# SNES_JAMMA.net
KiCad netlist of a schematic drawn in EAGLE
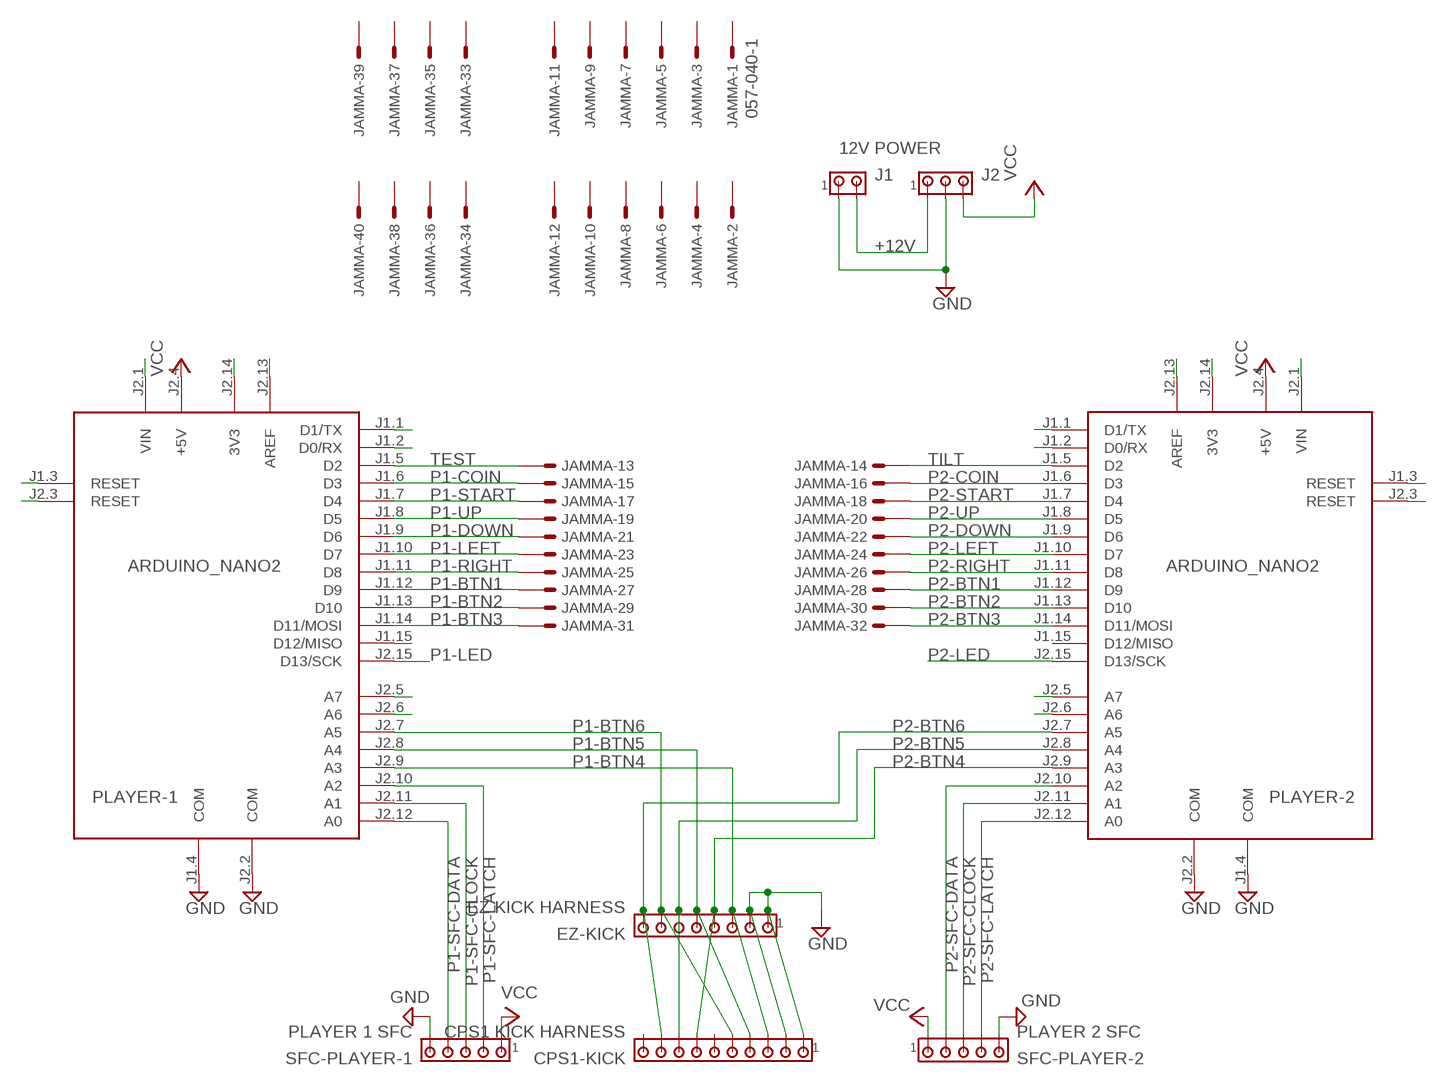
[diagram p0: schematic, sheet 1]

(export (version "E")
  (design (tool "Eeschema 10.0.6"))
  (components
    (comp (ref "CPS1-KICK")
      (value "CPS1 KICK HARNESS")
      (footprint "eagle-import:10X10MTA")
      (libsource (lib "eagle-import") (part "MTA10-100"))
    )
    (comp (ref "EZ-KICK")
      (value "EZ KICK HARNESS")
      (footprint "eagle-import:10X08MTA")
      (libsource (lib "eagle-import") (part "MTA08-100"))
    )
    (comp (ref "J1")
      (value "12V POWER")
      (footprint "eagle-import:10X02MTA")
      (libsource (lib "eagle-import") (part "MTA02-100"))
    )
    (comp (ref "J2")
      (value "MTA03-100")
      (footprint "eagle-import:10X03MTA")
      (libsource (lib "eagle-import") (part "MTA03-100"))
    )
    (comp (ref "JAMMA")
      (value "057-040-1")
      (footprint "eagle-import:057-040-1")
      (libsource (lib "eagle-import") (part "057-040-1"))
    )
    (comp (ref "PLAYER-1")
      (value "ARDUINO_NANO2")
      (footprint "eagle-import:ARDUINO_NANO2")
      (libsource (lib "eagle-import") (part "ARDUINO_NANO2"))
    )
    (comp (ref "PLAYER-2")
      (value "ARDUINO_NANO2")
      (footprint "eagle-import:ARDUINO_NANO2")
      (libsource (lib "eagle-import") (part "ARDUINO_NANO2"))
    )
    (comp (ref "SFC-PLAYER-1")
      (value "PLAYER 1 SFC")
      (footprint "eagle-import:10X05MTA")
      (libsource (lib "eagle-import") (part "MTA05-100"))
    )
    (comp (ref "SFC-PLAYER-2")
      (value "PLAYER 2 SFC")
      (footprint "eagle-import:10X05MTA")
      (libsource (lib "eagle-import") (part "MTA05-100"))
    )
  )
  (nets
    (net (code "1") (name "/+12V") (class "Default")
      (node (ref "J1") (pin "2") (pinfunction "2_2") (pintype "passive"))
      (node (ref "J2") (pin "1") (pinfunction "1_1") (pintype "passive"))
    )
    (net (code "2") (name "/P1-BTN1") (class "Default")
      (node (ref "JAMMA") (pin "27") (pinfunction "S_27") (pintype "passive"))
      (node (ref "PLAYER-1") (pin "J1.12") (pinfunction "D9_J1.12") (pintype "bidirectional"))
    )
    (net (code "3") (name "/P1-BTN2") (class "Default")
      (node (ref "JAMMA") (pin "29") (pinfunction "S_29") (pintype "passive"))
      (node (ref "PLAYER-1") (pin "J1.13") (pinfunction "D10_J1.13") (pintype "bidirectional"))
    )
    (net (code "4") (name "/P1-BTN3") (class "Default")
      (node (ref "JAMMA") (pin "31") (pinfunction "S_31") (pintype "passive"))
      (node (ref "PLAYER-1") (pin "J1.14") (pinfunction "D11/MOSI_J1.14") (pintype "bidirectional"))
    )
    (net (code "5") (name "/P1-BTN4") (class "Default")
      (node (ref "CPS1-KICK") (pin "3") (pinfunction "3_3") (pintype "passive"))
      (node (ref "EZ-KICK") (pin "3") (pinfunction "3_3") (pintype "passive"))
      (node (ref "PLAYER-1") (pin "J2.9") (pinfunction "A3_J2.9") (pintype "bidirectional"))
    )
    (net (code "6") (name "/P1-BTN5") (class "Default")
      (node (ref "CPS1-KICK") (pin "4") (pinfunction "4_4") (pintype "passive"))
      (node (ref "EZ-KICK") (pin "5") (pinfunction "5_5") (pintype "passive"))
      (node (ref "PLAYER-1") (pin "J2.8") (pinfunction "A4_J2.8") (pintype "bidirectional"))
    )
    (net (code "7") (name "/P1-BTN6") (class "Default")
      (node (ref "CPS1-KICK") (pin "5") (pinfunction "5_5") (pintype "passive"))
      (node (ref "EZ-KICK") (pin "7") (pinfunction "7_7") (pintype "passive"))
      (node (ref "PLAYER-1") (pin "J2.7") (pinfunction "A5_J2.7") (pintype "bidirectional"))
    )
    (net (code "8") (name "/P1-COIN") (class "Default")
      (node (ref "JAMMA") (pin "15") (pinfunction "S_15") (pintype "passive"))
      (node (ref "PLAYER-1") (pin "J1.6") (pinfunction "D3_J1.6") (pintype "bidirectional"))
    )
    (net (code "9") (name "/P1-DOWN") (class "Default")
      (node (ref "JAMMA") (pin "21") (pinfunction "S_21") (pintype "passive"))
      (node (ref "PLAYER-1") (pin "J1.9") (pinfunction "D6_J1.9") (pintype "bidirectional"))
    )
    (net (code "10") (name "/P1-LED") (class "Default")
      (node (ref "PLAYER-1") (pin "J2.15") (pinfunction "D13/SCK_J2.15") (pintype "bidirectional"))
    )
    (net (code "11") (name "/P1-LEFT") (class "Default")
      (node (ref "JAMMA") (pin "23") (pinfunction "S_23") (pintype "passive"))
      (node (ref "PLAYER-1") (pin "J1.10") (pinfunction "D7_J1.10") (pintype "bidirectional"))
    )
    (net (code "12") (name "/P1-RIGHT") (class "Default")
      (node (ref "JAMMA") (pin "25") (pinfunction "S_25") (pintype "passive"))
      (node (ref "PLAYER-1") (pin "J1.11") (pinfunction "D8_J1.11") (pintype "bidirectional"))
    )
    (net (code "13") (name "/P1-SFC-CLOCK") (class "Default")
      (node (ref "PLAYER-1") (pin "J2.11") (pinfunction "A1_J2.11") (pintype "bidirectional"))
      (node (ref "SFC-PLAYER-1") (pin "3") (pinfunction "3_3") (pintype "passive"))
    )
    (net (code "14") (name "/P1-SFC-DATA") (class "Default")
      (node (ref "PLAYER-1") (pin "J2.12") (pinfunction "A0_J2.12") (pintype "bidirectional"))
      (node (ref "SFC-PLAYER-1") (pin "4") (pinfunction "4_4") (pintype "passive"))
    )
    (net (code "15") (name "/P1-SFC-LATCH") (class "Default")
      (node (ref "PLAYER-1") (pin "J2.10") (pinfunction "A2_J2.10") (pintype "bidirectional"))
      (node (ref "SFC-PLAYER-1") (pin "2") (pinfunction "2_2") (pintype "passive"))
    )
    (net (code "16") (name "/P1-START") (class "Default")
      (node (ref "JAMMA") (pin "17") (pinfunction "S_17") (pintype "passive"))
      (node (ref "PLAYER-1") (pin "J1.7") (pinfunction "D4_J1.7") (pintype "bidirectional"))
    )
    (net (code "17") (name "/P1-UP") (class "Default")
      (node (ref "JAMMA") (pin "19") (pinfunction "S_19") (pintype "passive"))
      (node (ref "PLAYER-1") (pin "J1.8") (pinfunction "D5_J1.8") (pintype "bidirectional"))
    )
    (net (code "18") (name "/P2-BTN1") (class "Default")
      (node (ref "JAMMA") (pin "28") (pinfunction "S_28") (pintype "passive"))
      (node (ref "PLAYER-2") (pin "J1.12") (pinfunction "D9_J1.12") (pintype "bidirectional"))
    )
    (net (code "19") (name "/P2-BTN2") (class "Default")
      (node (ref "JAMMA") (pin "30") (pinfunction "S_30") (pintype "passive"))
      (node (ref "PLAYER-2") (pin "J1.13") (pinfunction "D10_J1.13") (pintype "bidirectional"))
    )
    (net (code "20") (name "/P2-BTN3") (class "Default")
      (node (ref "JAMMA") (pin "32") (pinfunction "S_32") (pintype "passive"))
      (node (ref "PLAYER-2") (pin "J1.14") (pinfunction "D11/MOSI_J1.14") (pintype "bidirectional"))
    )
    (net (code "21") (name "/P2-BTN4") (class "Default")
      (node (ref "CPS1-KICK") (pin "7") (pinfunction "7_7") (pintype "passive"))
      (node (ref "EZ-KICK") (pin "4") (pinfunction "4_4") (pintype "passive"))
      (node (ref "PLAYER-2") (pin "J2.9") (pinfunction "A3_J2.9") (pintype "bidirectional"))
    )
    (net (code "22") (name "/P2-BTN5") (class "Default")
      (node (ref "CPS1-KICK") (pin "8") (pinfunction "8_8") (pintype "passive"))
      (node (ref "EZ-KICK") (pin "6") (pinfunction "6_6") (pintype "passive"))
      (node (ref "PLAYER-2") (pin "J2.8") (pinfunction "A4_J2.8") (pintype "bidirectional"))
    )
    (net (code "23") (name "/P2-BTN6") (class "Default")
      (node (ref "CPS1-KICK") (pin "9") (pinfunction "9_9") (pintype "passive"))
      (node (ref "EZ-KICK") (pin "8") (pinfunction "8_8") (pintype "passive"))
      (node (ref "PLAYER-2") (pin "J2.7") (pinfunction "A5_J2.7") (pintype "bidirectional"))
    )
    (net (code "24") (name "/P2-COIN") (class "Default")
      (node (ref "JAMMA") (pin "16") (pinfunction "S_16") (pintype "passive"))
      (node (ref "PLAYER-2") (pin "J1.6") (pinfunction "D3_J1.6") (pintype "bidirectional"))
    )
    (net (code "25") (name "/P2-DOWN") (class "Default")
      (node (ref "JAMMA") (pin "22") (pinfunction "S_22") (pintype "passive"))
      (node (ref "PLAYER-2") (pin "J1.9") (pinfunction "D6_J1.9") (pintype "bidirectional"))
    )
    (net (code "26") (name "/P2-LED") (class "Default")
      (node (ref "PLAYER-2") (pin "J2.15") (pinfunction "D13/SCK_J2.15") (pintype "bidirectional"))
    )
    (net (code "27") (name "/P2-LEFT") (class "Default")
      (node (ref "JAMMA") (pin "24") (pinfunction "S_24") (pintype "passive"))
      (node (ref "PLAYER-2") (pin "J1.10") (pinfunction "D7_J1.10") (pintype "bidirectional"))
    )
    (net (code "28") (name "/P2-RIGHT") (class "Default")
      (node (ref "JAMMA") (pin "26") (pinfunction "S_26") (pintype "passive"))
      (node (ref "PLAYER-2") (pin "J1.11") (pinfunction "D8_J1.11") (pintype "bidirectional"))
    )
    (net (code "29") (name "/P2-SFC-CLOCK") (class "Default")
      (node (ref "PLAYER-2") (pin "J2.11") (pinfunction "A1_J2.11") (pintype "bidirectional"))
      (node (ref "SFC-PLAYER-2") (pin "3") (pinfunction "3_3") (pintype "passive"))
    )
    (net (code "30") (name "/P2-SFC-DATA") (class "Default")
      (node (ref "PLAYER-2") (pin "J2.12") (pinfunction "A0_J2.12") (pintype "bidirectional"))
      (node (ref "SFC-PLAYER-2") (pin "4") (pinfunction "4_4") (pintype "passive"))
    )
    (net (code "31") (name "/P2-SFC-LATCH") (class "Default")
      (node (ref "PLAYER-2") (pin "J2.10") (pinfunction "A2_J2.10") (pintype "bidirectional"))
      (node (ref "SFC-PLAYER-2") (pin "2") (pinfunction "2_2") (pintype "passive"))
    )
    (net (code "32") (name "/P2-START") (class "Default")
      (node (ref "JAMMA") (pin "18") (pinfunction "S_18") (pintype "passive"))
      (node (ref "PLAYER-2") (pin "J1.7") (pinfunction "D4_J1.7") (pintype "bidirectional"))
    )
    (net (code "33") (name "/P2-UP") (class "Default")
      (node (ref "JAMMA") (pin "20") (pinfunction "S_20") (pintype "passive"))
      (node (ref "PLAYER-2") (pin "J1.8") (pinfunction "D5_J1.8") (pintype "bidirectional"))
    )
    (net (code "34") (name "/TEST") (class "Default")
      (node (ref "JAMMA") (pin "13") (pinfunction "S_13") (pintype "passive"))
      (node (ref "PLAYER-1") (pin "J1.5") (pinfunction "D2_J1.5") (pintype "bidirectional"))
    )
    (net (code "35") (name "/TILT") (class "Default")
      (node (ref "JAMMA") (pin "14") (pinfunction "S_14") (pintype "passive"))
      (node (ref "PLAYER-2") (pin "J1.5") (pinfunction "D2_J1.5") (pintype "bidirectional"))
    )
    (net (code "36") (name "GND") (class "Default")
      (node (ref "CPS1-KICK") (pin "1") (pinfunction "1_1") (pintype "passive"))
      (node (ref "CPS1-KICK") (pin "2") (pinfunction "2_2") (pintype "passive"))
      (node (ref "EZ-KICK") (pin "1") (pinfunction "1_1") (pintype "passive"))
      (node (ref "EZ-KICK") (pin "2") (pinfunction "2_2") (pintype "passive"))
      (node (ref "J1") (pin "1") (pinfunction "1_1") (pintype "passive"))
      (node (ref "J2") (pin "2") (pinfunction "2_2") (pintype "passive"))
      (node (ref "PLAYER-1") (pin "J1.4") (pinfunction "COM_J1.4") (pintype "power_in"))
      (node (ref "PLAYER-1") (pin "J2.2") (pinfunction "COM_J2.2") (pintype "power_in"))
      (node (ref "PLAYER-2") (pin "J1.4") (pinfunction "COM_J1.4") (pintype "power_in"))
      (node (ref "PLAYER-2") (pin "J2.2") (pinfunction "COM_J2.2") (pintype "power_in"))
      (node (ref "SFC-PLAYER-1") (pin "5") (pinfunction "5_5") (pintype "passive"))
      (node (ref "SFC-PLAYER-2") (pin "5") (pinfunction "5_5") (pintype "passive"))
    )
    (net (code "37") (name "VCC") (class "Default")
      (node (ref "J2") (pin "3") (pinfunction "3_3") (pintype "passive"))
      (node (ref "PLAYER-1") (pin "J2.4") (pinfunction "+5V_J2.4") (pintype "power_in"))
      (node (ref "PLAYER-2") (pin "J2.4") (pinfunction "+5V_J2.4") (pintype "power_in"))
      (node (ref "SFC-PLAYER-1") (pin "1") (pinfunction "1_1") (pintype "passive"))
      (node (ref "SFC-PLAYER-2") (pin "1") (pinfunction "1_1") (pintype "passive"))
    )
    (net (code "38") (name "unconnected-(CPS1-KICK-Pad6)") (class "Default")
      (node (ref "CPS1-KICK") (pin "6") (pinfunction "6_6") (pintype "passive"))
    )
    (net (code "39") (name "unconnected-(CPS1-KICK-Pad10)") (class "Default")
      (node (ref "CPS1-KICK") (pin "10") (pinfunction "10_10") (pintype "passive"))
    )
    (net (code "40") (name "unconnected-(JAMMAA-S-Pad1)") (class "Default")
      (node (ref "JAMMA") (pin "1") (pinfunction "S_1") (pintype "passive"))
    )
    (net (code "41") (name "unconnected-(JAMMAAA-S-Pad33)") (class "Default")
      (node (ref "JAMMA") (pin "33") (pinfunction "S_33") (pintype "passive"))
    )
    (net (code "42") (name "unconnected-(JAMMAAB-S-Pad34)") (class "Default")
      (node (ref "JAMMA") (pin "34") (pinfunction "S_34") (pintype "passive"))
    )
    (net (code "43") (name "unconnected-(JAMMAAC-S-Pad35)") (class "Default")
      (node (ref "JAMMA") (pin "35") (pinfunction "S_35") (pintype "passive"))
    )
    (net (code "44") (name "unconnected-(JAMMAAD-S-Pad36)") (class "Default")
      (node (ref "JAMMA") (pin "36") (pinfunction "S_36") (pintype "passive"))
    )
    (net (code "45") (name "unconnected-(JAMMAAE-S-Pad37)") (class "Default")
      (node (ref "JAMMA") (pin "37") (pinfunction "S_37") (pintype "passive"))
    )
    (net (code "46") (name "unconnected-(JAMMAAF-S-Pad38)") (class "Default")
      (node (ref "JAMMA") (pin "38") (pinfunction "S_38") (pintype "passive"))
    )
    (net (code "47") (name "unconnected-(JAMMAAG-S-Pad39)") (class "Default")
      (node (ref "JAMMA") (pin "39") (pinfunction "S_39") (pintype "passive"))
    )
    (net (code "48") (name "unconnected-(JAMMAAH-S-Pad4)") (class "Default")
      (node (ref "JAMMA") (pin "4") (pinfunction "S_4") (pintype "passive"))
    )
    (net (code "49") (name "unconnected-(JAMMAAI-S-Pad40)") (class "Default")
      (node (ref "JAMMA") (pin "40") (pinfunction "S_40") (pintype "passive"))
    )
    (net (code "50") (name "unconnected-(JAMMAAJ-S-Pad5)") (class "Default")
      (node (ref "JAMMA") (pin "5") (pinfunction "S_5") (pintype "passive"))
    )
    (net (code "51") (name "unconnected-(JAMMAAK-S-Pad6)") (class "Default")
      (node (ref "JAMMA") (pin "6") (pinfunction "S_6") (pintype "passive"))
    )
    (net (code "52") (name "unconnected-(JAMMAAL-S-Pad7)") (class "Default")
      (node (ref "JAMMA") (pin "7") (pinfunction "S_7") (pintype "passive"))
    )
    (net (code "53") (name "unconnected-(JAMMAAM-S-Pad8)") (class "Default")
      (node (ref "JAMMA") (pin "8") (pinfunction "S_8") (pintype "passive"))
    )
    (net (code "54") (name "unconnected-(JAMMAAN-S-Pad9)") (class "Default")
      (node (ref "JAMMA") (pin "9") (pinfunction "S_9") (pintype "passive"))
    )
    (net (code "55") (name "unconnected-(JAMMAB-S-Pad10)") (class "Default")
      (node (ref "JAMMA") (pin "10") (pinfunction "S_10") (pintype "passive"))
    )
    (net (code "56") (name "unconnected-(JAMMAC-S-Pad11)") (class "Default")
      (node (ref "JAMMA") (pin "11") (pinfunction "S_11") (pintype "passive"))
    )
    (net (code "57") (name "unconnected-(JAMMAD-S-Pad12)") (class "Default")
      (node (ref "JAMMA") (pin "12") (pinfunction "S_12") (pintype "passive"))
    )
    (net (code "58") (name "unconnected-(JAMMAL-S-Pad2)") (class "Default")
      (node (ref "JAMMA") (pin "2") (pinfunction "S_2") (pintype "passive"))
    )
    (net (code "59") (name "unconnected-(JAMMAW-S-Pad3)") (class "Default")
      (node (ref "JAMMA") (pin "3") (pinfunction "S_3") (pintype "passive"))
    )
    (net (code "60") (name "unconnected-(PLAYER-1-3V3-PadJ2.14)") (class "Default")
      (node (ref "PLAYER-1") (pin "J2.14") (pinfunction "3V3_J2.14") (pintype "power_in"))
    )
    (net (code "61") (name "unconnected-(PLAYER-1-A6-PadJ2.6)") (class "Default")
      (node (ref "PLAYER-1") (pin "J2.6") (pinfunction "A6_J2.6") (pintype "bidirectional"))
    )
    (net (code "62") (name "unconnected-(PLAYER-1-A7-PadJ2.5)") (class "Default")
      (node (ref "PLAYER-1") (pin "J2.5") (pinfunction "A7_J2.5") (pintype "bidirectional"))
    )
    (net (code "63") (name "unconnected-(PLAYER-1-AREF-PadJ2.13)") (class "Default")
      (node (ref "PLAYER-1") (pin "J2.13") (pinfunction "AREF_J2.13") (pintype "power_in"))
    )
    (net (code "64") (name "unconnected-(PLAYER-1-D0{slash}RX-PadJ1.2)") (class "Default")
      (node (ref "PLAYER-1") (pin "J1.2") (pinfunction "D0/RX_J1.2") (pintype "bidirectional"))
    )
    (net (code "65") (name "unconnected-(PLAYER-1-D1{slash}TX-PadJ1.1)") (class "Default")
      (node (ref "PLAYER-1") (pin "J1.1") (pinfunction "D1/TX_J1.1") (pintype "bidirectional"))
    )
    (net (code "66") (name "unconnected-(PLAYER-1-D12{slash}MISO-PadJ1.15)") (class "Default")
      (node (ref "PLAYER-1") (pin "J1.15") (pinfunction "D12/MISO_J1.15") (pintype "bidirectional"))
    )
    (net (code "67") (name "unconnected-(PLAYER-1-RESET-PadJ1.3)") (class "Default")
      (node (ref "PLAYER-1") (pin "J1.3") (pinfunction "RESET_J1.3") (pintype "bidirectional"))
    )
    (net (code "68") (name "unconnected-(PLAYER-1-RESET-PadJ2.3)") (class "Default")
      (node (ref "PLAYER-1") (pin "J2.3") (pinfunction "RESET_J2.3") (pintype "bidirectional"))
    )
    (net (code "69") (name "unconnected-(PLAYER-1-VIN-PadJ2.1)") (class "Default")
      (node (ref "PLAYER-1") (pin "J2.1") (pinfunction "VIN_J2.1") (pintype "power_in"))
    )
    (net (code "70") (name "unconnected-(PLAYER-2-3V3-PadJ2.14)") (class "Default")
      (node (ref "PLAYER-2") (pin "J2.14") (pinfunction "3V3_J2.14") (pintype "power_in"))
    )
    (net (code "71") (name "unconnected-(PLAYER-2-A6-PadJ2.6)") (class "Default")
      (node (ref "PLAYER-2") (pin "J2.6") (pinfunction "A6_J2.6") (pintype "bidirectional"))
    )
    (net (code "72") (name "unconnected-(PLAYER-2-A7-PadJ2.5)") (class "Default")
      (node (ref "PLAYER-2") (pin "J2.5") (pinfunction "A7_J2.5") (pintype "bidirectional"))
    )
    (net (code "73") (name "unconnected-(PLAYER-2-AREF-PadJ2.13)") (class "Default")
      (node (ref "PLAYER-2") (pin "J2.13") (pinfunction "AREF_J2.13") (pintype "power_in"))
    )
    (net (code "74") (name "unconnected-(PLAYER-2-D0{slash}RX-PadJ1.2)") (class "Default")
      (node (ref "PLAYER-2") (pin "J1.2") (pinfunction "D0/RX_J1.2") (pintype "bidirectional"))
    )
    (net (code "75") (name "unconnected-(PLAYER-2-D1{slash}TX-PadJ1.1)") (class "Default")
      (node (ref "PLAYER-2") (pin "J1.1") (pinfunction "D1/TX_J1.1") (pintype "bidirectional"))
    )
    (net (code "76") (name "unconnected-(PLAYER-2-D12{slash}MISO-PadJ1.15)") (class "Default")
      (node (ref "PLAYER-2") (pin "J1.15") (pinfunction "D12/MISO_J1.15") (pintype "bidirectional"))
    )
    (net (code "77") (name "unconnected-(PLAYER-2-RESET-PadJ1.3)") (class "Default")
      (node (ref "PLAYER-2") (pin "J1.3") (pinfunction "RESET_J1.3") (pintype "bidirectional"))
    )
    (net (code "78") (name "unconnected-(PLAYER-2-RESET-PadJ2.3)") (class "Default")
      (node (ref "PLAYER-2") (pin "J2.3") (pinfunction "RESET_J2.3") (pintype "bidirectional"))
    )
    (net (code "79") (name "unconnected-(PLAYER-2-VIN-PadJ2.1)") (class "Default")
      (node (ref "PLAYER-2") (pin "J2.1") (pinfunction "VIN_J2.1") (pintype "power_in"))
    )
  )
)
